# PWR_BootBat.net
KiCad netlist of a schematic drawn in Altium Designer
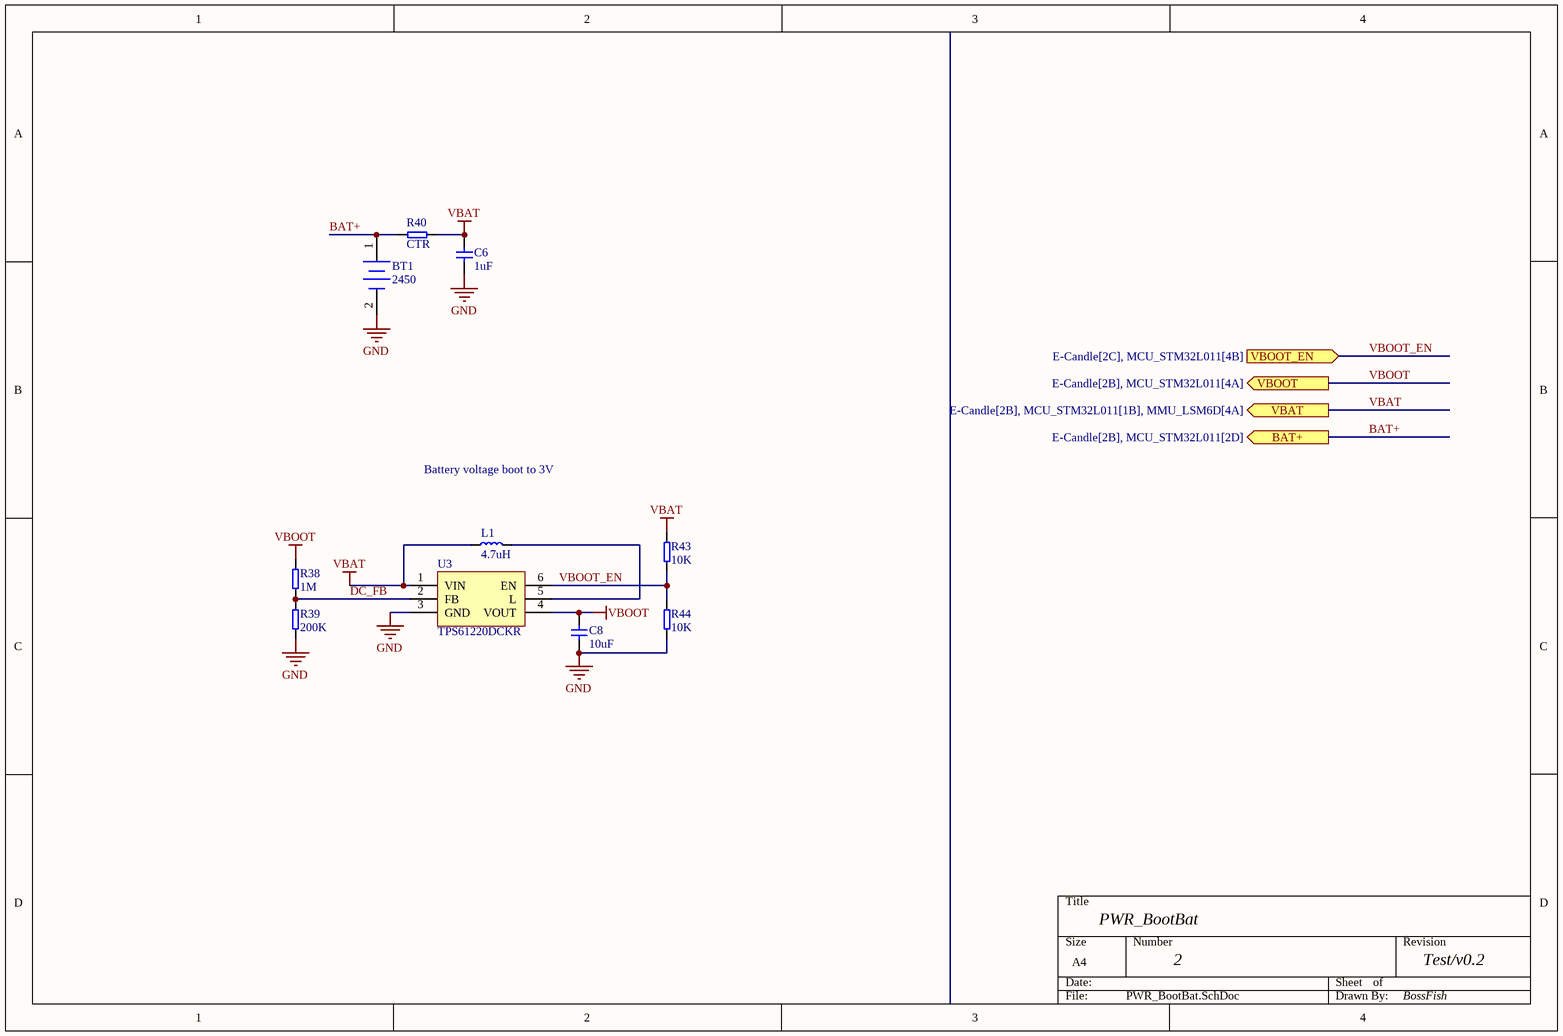
[diagram p0: PWR_BootBat.SchDoc]

(export (version "E")
  (design (tool "Eeschema 10.0.6"))
  (components
    (comp (ref "BT1")
      (value "2450")
      (footprint "CR2450_CJ")
      (description "Multicell Battery")
      (fields (field (name "PUBLISHER") "Altium Limited"))
      (libsource (lib "Miscellaneous Devices") (part "Battery"))
    )
    (comp (ref "C6") (value "1uF") (footprint "0603-C") (libsource (lib "Schlib1") (part "Cap")))
    (comp (ref "C8") (value "10uF") (footprint "0603-C") (libsource (lib "Schlib1") (part "Cap")))
    (comp (ref "L1") (value "4.7uH") (footprint "0805-L") (libsource (lib "Schlib1") (part "Inductor")))
    (comp (ref "R38") (value "1M") (footprint "0603-R") (libsource (lib "Schlib1") (part "Res")))
    (comp (ref "R39") (value "200K") (footprint "0603-R") (libsource (lib "Schlib1") (part "Res")))
    (comp (ref "R40") (value "CTR") (footprint "0603-R") (libsource (lib "Schlib1") (part "Res")))
    (comp (ref "R43") (value "10K") (footprint "0603-R") (libsource (lib "Schlib1") (part "Res")))
    (comp (ref "R44") (value "10K") (footprint "0603-R") (libsource (lib "Schlib1") (part "Res")))
    (comp (ref "U3")
      (value "TPS61220DCKR")
      (footprint "SC-70-6")
      (description "TPS6122x Low Input Voltage, 0.7V Boost Converter With 5.5μA Quiescent Current")
      (libsource (lib "Schlib1") (part "TPS61220DCKR"))
    )
  )
  (nets
    (net (code "1") (name "/BAT+") (class "Default")
      (node (ref "BT1") (pin "1") (pinfunction "+_1") (pintype "passive"))
      (node (ref "R40") (pin "2") (pinfunction "2_2") (pintype "passive"))
    )
    (net (code "2") (name "/DC_FB") (class "Default")
      (node (ref "R38") (pin "1") (pinfunction "1_1") (pintype "passive"))
      (node (ref "R39") (pin "2") (pinfunction "2_2") (pintype "passive"))
      (node (ref "U3") (pin "2") (pinfunction "FB_2") (pintype "passive"))
    )
    (net (code "3") (name "/VBOOT_EN") (class "Default")
      (node (ref "R43") (pin "1") (pinfunction "1_1") (pintype "passive"))
      (node (ref "R44") (pin "2") (pinfunction "2_2") (pintype "passive"))
      (node (ref "U3") (pin "6") (pinfunction "EN_6") (pintype "passive"))
    )
    (net (code "4") (name "GND") (class "Default")
      (node (ref "BT1") (pin "2") (pinfunction "-_2") (pintype "passive"))
      (node (ref "C6") (pin "1") (pinfunction "1_1") (pintype "passive"))
      (node (ref "C8") (pin "1") (pinfunction "1_1") (pintype "passive"))
      (node (ref "R39") (pin "1") (pinfunction "1_1") (pintype "passive"))
      (node (ref "R44") (pin "1") (pinfunction "1_1") (pintype "passive"))
      (node (ref "U3") (pin "3") (pinfunction "GND_3") (pintype "passive"))
    )
    (net (code "5") (name "Net-(U3-L)") (class "Default")
      (node (ref "L1") (pin "2") (pinfunction "2_2") (pintype "passive"))
      (node (ref "U3") (pin "5") (pinfunction "L_5") (pintype "passive"))
    )
    (net (code "6") (name "VBAT") (class "Default")
      (node (ref "C6") (pin "2") (pinfunction "2_2") (pintype "passive"))
      (node (ref "L1") (pin "1") (pinfunction "1_1") (pintype "passive"))
      (node (ref "R40") (pin "1") (pinfunction "1_1") (pintype "passive"))
      (node (ref "R43") (pin "2") (pinfunction "2_2") (pintype "passive"))
      (node (ref "U3") (pin "1") (pinfunction "VIN_1") (pintype "passive"))
    )
    (net (code "7") (name "VBOOT") (class "Default")
      (node (ref "C8") (pin "2") (pinfunction "2_2") (pintype "passive"))
      (node (ref "R38") (pin "2") (pinfunction "2_2") (pintype "passive"))
      (node (ref "U3") (pin "4") (pinfunction "VOUT_4") (pintype "passive"))
    )
  )
)
